# solar.net
KiCad netlist of a schematic drawn in Altium Designer
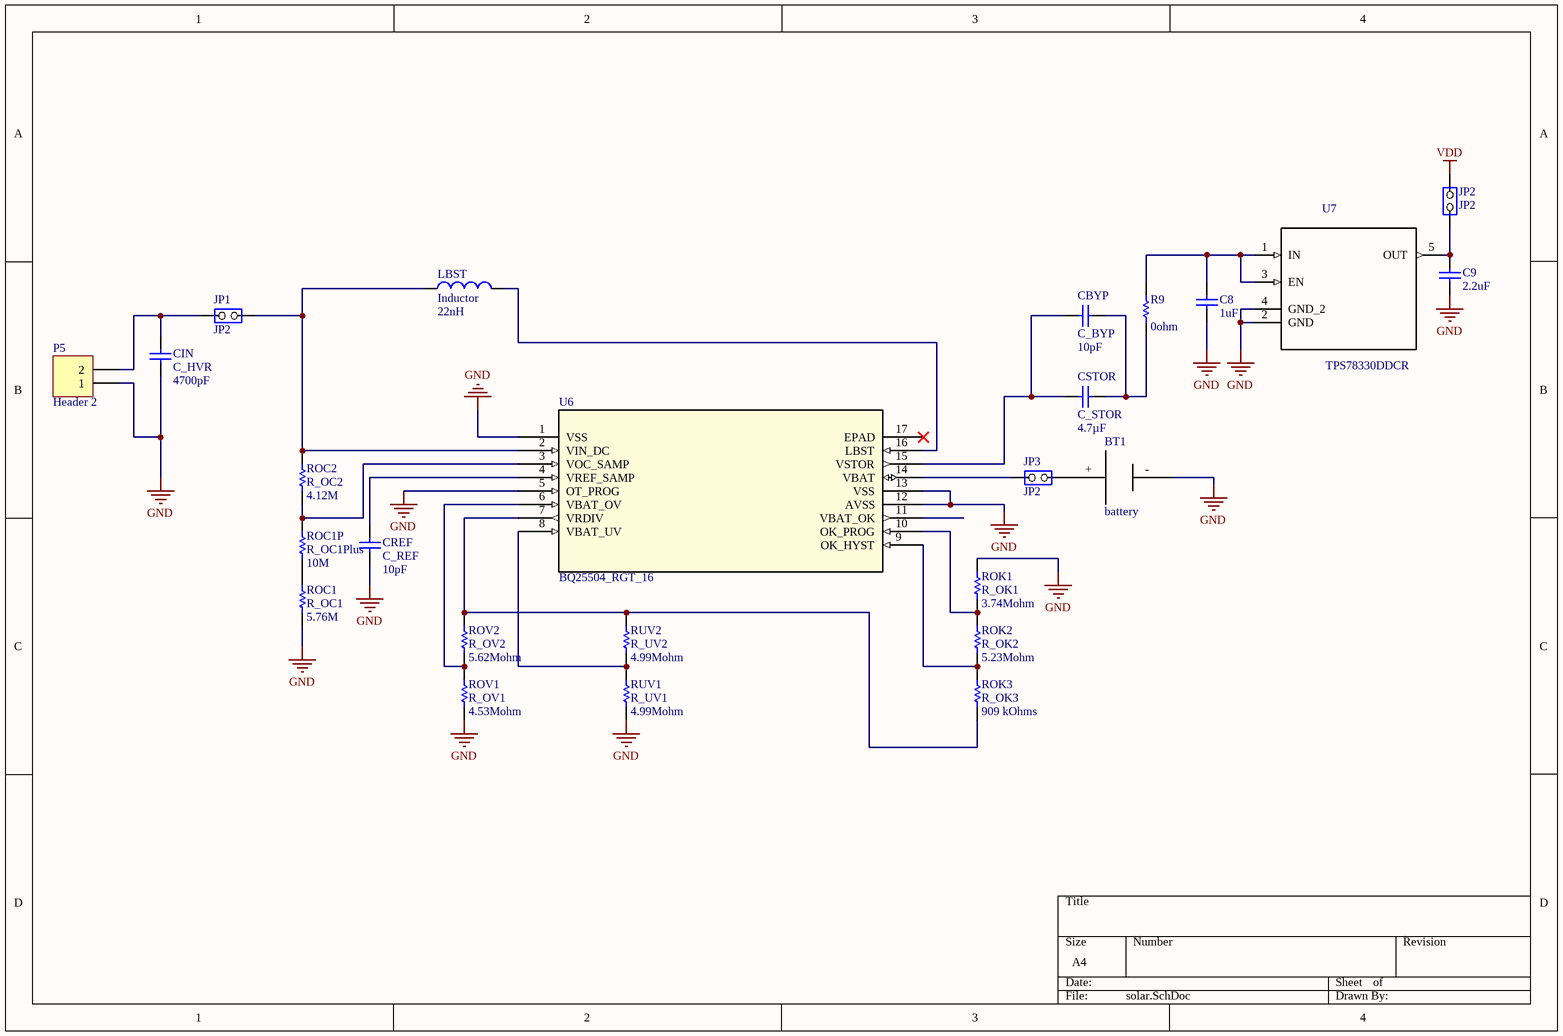
[diagram p0: solar.SchDoc]

(export (version "E")
  (design (tool "Eeschema 10.0.6"))
  (components
    (comp (ref "BT1")
      (value "battery")
      (footprint "BATTERY")
      (fields (field (name "MANUFACTURER") "Harwin Inc."))
      (libsource (lib "seeds") (part "battery"))
    )
    (comp (ref "C8")
      (value "1uF")
      (footprint "0603C")
      (description "Capacitor")
      (fields (field (name "MANUFACTURER") "AVX Corporation") (field (name "PUBLISHER") "Altium Limited"))
      (libsource (lib "MB1136") (part "Cap"))
    )
    (comp (ref "C9")
      (value "2.2uF")
      (footprint "0603C")
      (description "Capacitor")
      (fields
        (field (name "MANUFACTURER") "Murata Electronics North America")
        (field (name "PUBLISHER") "Altium Limited")
      )
      (libsource (lib "MB1136") (part "Cap"))
    )
    (comp (ref "CBYP")
      (value "C_BYP")
      (footprint "0603C")
      (description "Capacitor")
      (fields
        (field (name "ALTIUM_VALUE") "10pF")
        (field (name "MANUFACTURER") "Murata Electronics North America")
        (field (name "PUBLISHER") "Altium Limited")
      )
      (libsource (lib "Miscellaneous Devices") (part "Cap"))
    )
    (comp (ref "CIN")
      (value "C_HVR")
      (footprint "0603C")
      (description "Capacitor")
      (fields
        (field (name "ALTIUM_VALUE") "4700pF")
        (field (name "MANUFACTURER") "TDK")
        (field (name "PUBLISHER") "Altium Limited")
      )
      (libsource (lib "Miscellaneous Devices") (part "Cap"))
    )
    (comp (ref "CREF")
      (value "C_REF")
      (footprint "0603C")
      (description "Capacitor")
      (fields
        (field (name "ALTIUM_VALUE") "10pF")
        (field (name "MANUFACTURER") "Murata Electronics North America")
        (field (name "PUBLISHER") "Altium Limited")
      )
      (libsource (lib "Miscellaneous Devices") (part "Cap"))
    )
    (comp (ref "CSTOR")
      (value "C_STOR")
      (footprint "0603C")
      (description "Capacitor")
      (fields
        (field (name "ALTIUM_VALUE") "4.7µF")
        (field (name "MANUFACTURER") "Taiyo Yuden")
        (field (name "PUBLISHER") "Altium Limited")
      )
      (libsource (lib "Miscellaneous Devices") (part "Cap"))
    )
    (comp (ref "JP1")
      (value "JP2")
      (footprint "SIP2/2.54")
      (fields (field (name "MANUFACTURER") "Harwin Inc."))
      (libsource (lib "MB1136") (part "JP2"))
    )
    (comp (ref "JP2")
      (value "JP2")
      (footprint "SIP2/2.54")
      (fields (field (name "MANUFACTURER") "Harwin Inc."))
      (libsource (lib "MB1136") (part "JP2"))
    )
    (comp (ref "JP3")
      (value "JP2")
      (footprint "SIP2/2.54")
      (fields (field (name "MANUFACTURER") "Harwin Inc."))
      (libsource (lib "MB1136") (part "JP2"))
    )
    (comp (ref "LBST")
      (value "Inductor")
      (footprint "INDC1608L")
      (fields
        (field (name "ALTIUM_VALUE") "22nH")
        (field (name "MANUFACTURER") "Johanson Technology")
        (field (name "PUBLISHER") "Altium Limited")
      )
      (libsource (lib "Miscellaneous Devices") (part "Inductor"))
    )
    (comp (ref "P5")
      (value "Header 2")
      (footprint "HDR1X2")
      (description "Header, 2-Pin")
      (fields (field (name "MANUFACTURER") "Harwin Inc.") (field (name "PUBLISHER") "Altium Limited"))
      (libsource (lib "Miscellaneous Connectors") (part "Header 2"))
    )
    (comp (ref "R9")
      (value "0ohm")
      (footprint "0603R")
      (description "Resistor")
      (fields (field (name "MANUFACTURER") "Yageo") (field (name "PUBLISHER") "Altium Limited"))
      (libsource (lib "Miscellaneous Devices") (part "Res1"))
    )
    (comp (ref "ROC1")
      (value "R_OC1")
      (footprint "0603R")
      (description "Resistor")
      (fields
        (field (name "ALTIUM_VALUE") "5.76M")
        (field (name "MANUFACTURER") "Vishay Dale")
        (field (name "PUBLISHER") "Altium Limited")
      )
      (libsource (lib "Miscellaneous Devices") (part "Res1"))
    )
    (comp (ref "ROC1P")
      (value "R_OC1Plus")
      (footprint "0603R")
      (description "Resistor")
      (fields
        (field (name "ALTIUM_VALUE") "10M")
        (field (name "MANUFACTURER") "Yageo")
        (field (name "PUBLISHER") "Altium Limited")
      )
      (libsource (lib "Miscellaneous Devices") (part "Res1"))
    )
    (comp (ref "ROC2")
      (value "R_OC2")
      (footprint "0603R")
      (description "Resistor")
      (fields
        (field (name "ALTIUM_VALUE") "4.12M")
        (field (name "MANUFACTURER") "Vishay Dale")
        (field (name "PUBLISHER") "Altium Limited")
      )
      (libsource (lib "Miscellaneous Devices") (part "Res1"))
    )
    (comp (ref "ROK1")
      (value "R_OK1")
      (footprint "0603R")
      (description "Resistor")
      (fields
        (field (name "ALTIUM_VALUE") "3.74Mohm")
        (field (name "MANUFACTURER") "Stackpole Electronics Inc.")
        (field (name "PUBLISHER") "Altium Limited")
      )
      (libsource (lib "Miscellaneous Devices") (part "Res1"))
    )
    (comp (ref "ROK2")
      (value "R_OK2")
      (footprint "0603R")
      (description "Resistor")
      (fields
        (field (name "ALTIUM_VALUE") "5.23Mohm")
        (field (name "MANUFACTURER") "Vishay Dale")
        (field (name "PUBLISHER") "Altium Limited")
      )
      (libsource (lib "Miscellaneous Devices") (part "Res1"))
    )
    (comp (ref "ROK3")
      (value "R_OK3")
      (footprint "0603R")
      (description "Resistor")
      (fields
        (field (name "ALTIUM_VALUE") "909 kOhms")
        (field (name "MANUFACTURER") "Yageo")
        (field (name "PUBLISHER") "Altium Limited")
      )
      (libsource (lib "Miscellaneous Devices") (part "Res1"))
    )
    (comp (ref "ROV1")
      (value "R_OV1")
      (footprint "0603R")
      (description "Resistor")
      (fields
        (field (name "ALTIUM_VALUE") "4.53Mohm")
        (field (name "MANUFACTURER") "Stackpole Electronics Inc.")
        (field (name "PUBLISHER") "Altium Limited")
      )
      (libsource (lib "Miscellaneous Devices") (part "Res1"))
    )
    (comp (ref "ROV2")
      (value "R_OV2")
      (footprint "0603R")
      (description "Resistor")
      (fields
        (field (name "ALTIUM_VALUE") "5.62Mohm")
        (field (name "MANUFACTURER") "Stackpole Electronics Inc.")
        (field (name "PUBLISHER") "Altium Limited")
      )
      (libsource (lib "Miscellaneous Devices") (part "Res1"))
    )
    (comp (ref "RUV1")
      (value "R_UV1")
      (footprint "0603R")
      (description "Resistor")
      (fields
        (field (name "ALTIUM_VALUE") "4.99Mohm")
        (field (name "MANUFACTURER") "Vishay Dale")
        (field (name "PUBLISHER") "Altium Limited")
      )
      (libsource (lib "Miscellaneous Devices") (part "Res1"))
    )
    (comp (ref "RUV2")
      (value "R_UV2")
      (footprint "0603R")
      (description "Resistor")
      (fields
        (field (name "ALTIUM_VALUE") "4.99Mohm")
        (field (name "MANUFACTURER") "Vishay Dale")
        (field (name "PUBLISHER") "Altium Limited")
      )
      (libsource (lib "Miscellaneous Devices") (part "Res1"))
    )
    (comp (ref "U6")
      (value "BQ25504_RGT_16")
      (footprint "RGT16_1P7X1P7")
      (description "Imported")
      (fields
        (field (name "MANUFACTURER") "Texas Instruments")
        (field (name "GENERIC_PART_NUMBER") "BQ25504")
      )
      (libsource (lib "BQ25504_battery_charger") (part "BQ25504_RGT_16"))
    )
    (comp (ref "U7")
      (value "TPS78330DDCR")
      (footprint "SOT95P280X110-5N")
      (description "IC REG LINEAR 3V 150MA SOT23-5")
      (fields (field (name "MF") "Texas Instruments"))
      (libsource (lib "TPS78330DDCR") (part "TPS78330DDCR"))
    )
  )
  (nets
    (net (code "1") (name "GND") (class "Default")
      (node (ref "BT1") (pin "-") (pintype "passive"))
      (node (ref "C8") (pin "1") (pinfunction "1_1") (pintype "passive"))
      (node (ref "C9") (pin "1") (pinfunction "1_1") (pintype "passive"))
      (node (ref "CIN") (pin "1") (pinfunction "1_1") (pintype "passive"))
      (node (ref "CREF") (pin "1") (pinfunction "1_1") (pintype "passive"))
      (node (ref "P5") (pin "1") (pinfunction "1_1") (pintype "passive"))
      (node (ref "ROC1") (pin "1") (pinfunction "1_1") (pintype "passive"))
      (node (ref "ROK1") (pin "2") (pinfunction "2_2") (pintype "passive"))
      (node (ref "ROV1") (pin "1") (pinfunction "1_1") (pintype "passive"))
      (node (ref "RUV1") (pin "1") (pinfunction "1_1") (pintype "passive"))
      (node (ref "U6") (pin "1") (pinfunction "VSS_1") (pintype "power_in"))
      (node (ref "U6") (pin "12") (pinfunction "AVSS_12") (pintype "power_in"))
      (node (ref "U6") (pin "13") (pinfunction "VSS_13") (pintype "power_in"))
      (node (ref "U6") (pin "5") (pinfunction "OT_PROG_5") (pintype "input"))
      (node (ref "U7") (pin "2") (pinfunction "GND_2") (pintype "passive"))
      (node (ref "U7") (pin "4") (pinfunction "GND_2_4") (pintype "passive"))
    )
    (net (code "2") (name "Net-(CBYP-Pad2)") (class "Default")
      (node (ref "CBYP") (pin "2") (pinfunction "2_2") (pintype "passive"))
      (node (ref "CSTOR") (pin "2") (pinfunction "2_2") (pintype "passive"))
      (node (ref "R9") (pin "1") (pinfunction "1_1") (pintype "passive"))
    )
    (net (code "3") (name "Net-(JP1-COMMON)") (class "Default")
      (node (ref "CIN") (pin "2") (pinfunction "2_2") (pintype "passive"))
      (node (ref "JP1") (pin "1") (pinfunction "COMMON_1") (pintype "passive"))
      (node (ref "P5") (pin "2") (pinfunction "2_2") (pintype "passive"))
    )
    (net (code "4") (name "Net-(JP1-NO)") (class "Default")
      (node (ref "JP1") (pin "2") (pinfunction "NO_2") (pintype "passive"))
      (node (ref "LBST") (pin "1") (pinfunction "1_1") (pintype "passive"))
      (node (ref "ROC2") (pin "2") (pinfunction "2_2") (pintype "passive"))
      (node (ref "U6") (pin "2") (pinfunction "VIN_DC_2") (pintype "input"))
    )
    (net (code "5") (name "Net-(JP2-COMMON)") (class "Default")
      (node (ref "C9") (pin "2") (pinfunction "2_2") (pintype "passive"))
      (node (ref "JP2") (pin "1") (pinfunction "COMMON_1") (pintype "passive"))
      (node (ref "U7") (pin "5") (pinfunction "OUT_5") (pintype "output"))
    )
    (net (code "6") (name "Net-(JP3-COMMON)") (class "Default")
      (node (ref "JP3") (pin "1") (pinfunction "COMMON_1") (pintype "passive"))
      (node (ref "U6") (pin "14") (pinfunction "VBAT_14") (pintype "bidirectional"))
    )
    (net (code "7") (name "Net-(JP3-NO)") (class "Default")
      (node (ref "BT1") (pin "+") (pintype "passive"))
      (node (ref "JP3") (pin "2") (pinfunction "NO_2") (pintype "passive"))
    )
    (net (code "8") (name "Net-(ROC1-Pad2)") (class "Default")
      (node (ref "ROC1") (pin "2") (pinfunction "2_2") (pintype "passive"))
      (node (ref "ROC1P") (pin "1") (pinfunction "1_1") (pintype "passive"))
    )
    (net (code "9") (name "Net-(U6-LBST)") (class "Default")
      (node (ref "LBST") (pin "2") (pinfunction "2_2") (pintype "passive"))
      (node (ref "U6") (pin "16") (pinfunction "LBST_16") (pintype "input"))
    )
    (net (code "10") (name "Net-(U6-OK_HYST)") (class "Default")
      (node (ref "ROK2") (pin "1") (pinfunction "1_1") (pintype "passive"))
      (node (ref "ROK3") (pin "2") (pinfunction "2_2") (pintype "passive"))
      (node (ref "U6") (pin "9") (pinfunction "OK_HYST_9") (pintype "input"))
    )
    (net (code "11") (name "Net-(U6-OK_PROG)") (class "Default")
      (node (ref "ROK1") (pin "1") (pinfunction "1_1") (pintype "passive"))
      (node (ref "ROK2") (pin "2") (pinfunction "2_2") (pintype "passive"))
      (node (ref "U6") (pin "10") (pinfunction "OK_PROG_10") (pintype "input"))
    )
    (net (code "12") (name "Net-(U6-VBAT_OV)") (class "Default")
      (node (ref "ROV1") (pin "2") (pinfunction "2_2") (pintype "passive"))
      (node (ref "ROV2") (pin "1") (pinfunction "1_1") (pintype "passive"))
      (node (ref "U6") (pin "6") (pinfunction "VBAT_OV_6") (pintype "input"))
    )
    (net (code "13") (name "Net-(U6-VBAT_UV)") (class "Default")
      (node (ref "RUV1") (pin "2") (pinfunction "2_2") (pintype "passive"))
      (node (ref "RUV2") (pin "1") (pinfunction "1_1") (pintype "passive"))
      (node (ref "U6") (pin "8") (pinfunction "VBAT_UV_8") (pintype "input"))
    )
    (net (code "14") (name "Net-(U6-VOC_SAMP)") (class "Default")
      (node (ref "ROC1P") (pin "2") (pinfunction "2_2") (pintype "passive"))
      (node (ref "ROC2") (pin "1") (pinfunction "1_1") (pintype "passive"))
      (node (ref "U6") (pin "3") (pinfunction "VOC_SAMP_3") (pintype "input"))
    )
    (net (code "15") (name "Net-(U6-VRDIV)") (class "Default")
      (node (ref "ROK3") (pin "1") (pinfunction "1_1") (pintype "passive"))
      (node (ref "ROV2") (pin "2") (pinfunction "2_2") (pintype "passive"))
      (node (ref "RUV2") (pin "2") (pinfunction "2_2") (pintype "passive"))
      (node (ref "U6") (pin "7") (pinfunction "VRDIV_7") (pintype "output"))
    )
    (net (code "16") (name "Net-(U6-VREF_SAMP)") (class "Default")
      (node (ref "CREF") (pin "2") (pinfunction "2_2") (pintype "passive"))
      (node (ref "U6") (pin "4") (pinfunction "VREF_SAMP_4") (pintype "input"))
    )
    (net (code "17") (name "Net-(U6-VSTOR)") (class "Default")
      (node (ref "CBYP") (pin "1") (pinfunction "1_1") (pintype "passive"))
      (node (ref "CSTOR") (pin "1") (pinfunction "1_1") (pintype "passive"))
      (node (ref "U6") (pin "15") (pinfunction "VSTOR_15") (pintype "output"))
    )
    (net (code "18") (name "Net-(U7-EN)") (class "Default")
      (node (ref "C8") (pin "2") (pinfunction "2_2") (pintype "passive"))
      (node (ref "R9") (pin "2") (pinfunction "2_2") (pintype "passive"))
      (node (ref "U7") (pin "1") (pinfunction "IN_1") (pintype "input"))
      (node (ref "U7") (pin "3") (pinfunction "EN_3") (pintype "input"))
    )
    (net (code "19") (name "VDD") (class "Default")
      (node (ref "JP2") (pin "2") (pinfunction "NO_2") (pintype "passive"))
    )
    (net (code "20") (name "unconnected-(U6-EPAD-Pad17)") (class "Default")
      (node (ref "U6") (pin "17") (pinfunction "EPAD_17") (pintype "power_in+no_connect"))
    )
    (net (code "21") (name "unconnected-(U6-VBAT_OK-Pad11)") (class "Default")
      (node (ref "U6") (pin "11") (pinfunction "VBAT_OK_11") (pintype "output"))
    )
  )
)
